# SidBerry_AriettaG25.net
KiCad netlist of a schematic drawn in EAGLE
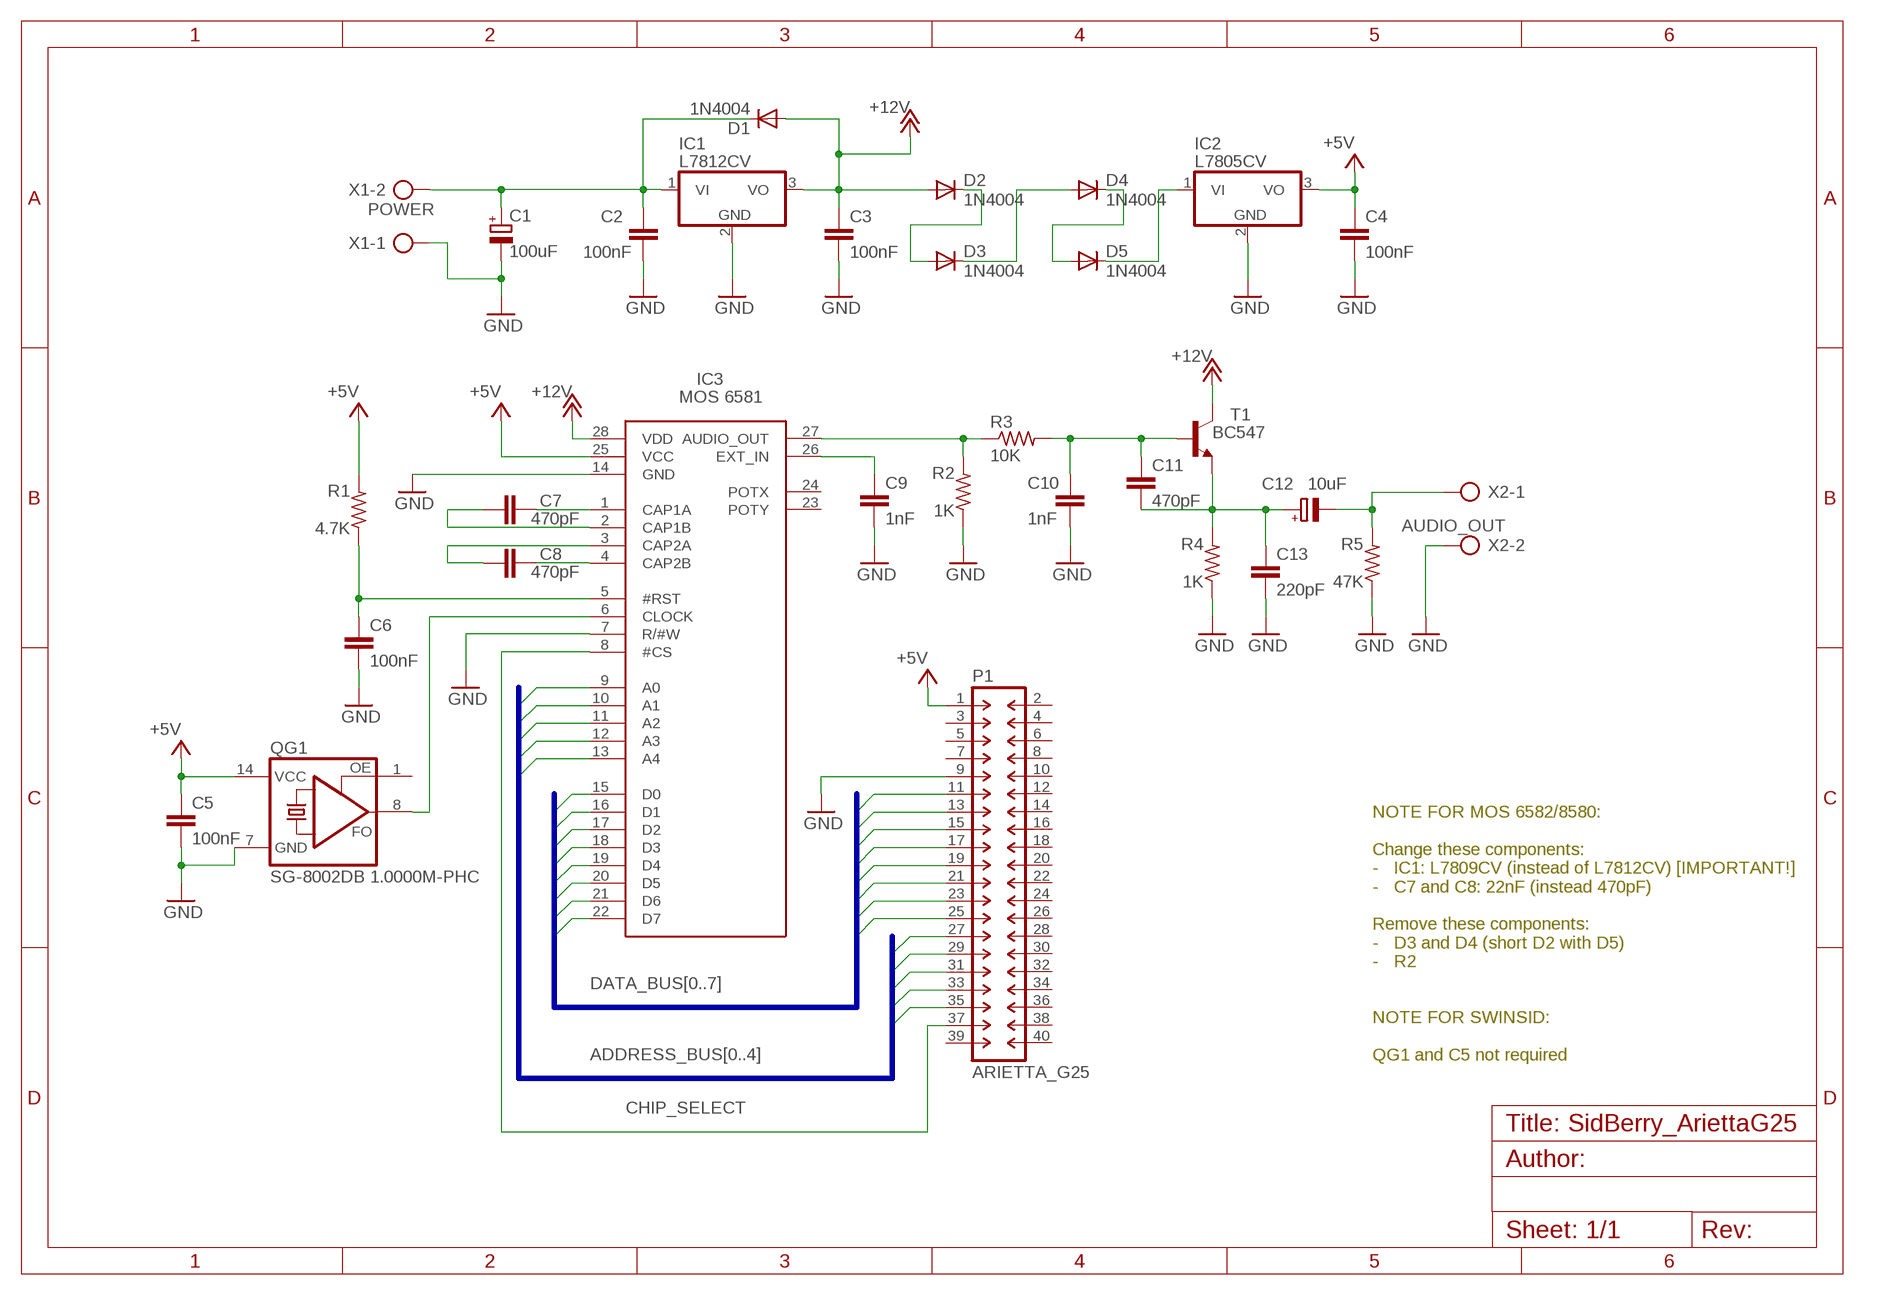
[diagram p0: schematic, sheet 1]

(export (version "E")
  (design (tool "Eeschema 10.0.6"))
  (components
    (comp (ref "C1")
      (value "100uF")
      (footprint "eagle-import:E2,5-6")
      (libsource (lib "eagle-import") (part "CPOL-EUE2.5-6"))
    )
    (comp (ref "C2")
      (value "100nF")
      (footprint "eagle-import:C025-024X044")
      (libsource (lib "eagle-import") (part "C-EU025-024X044"))
    )
    (comp (ref "C3")
      (value "100nF")
      (footprint "eagle-import:C025-024X044")
      (libsource (lib "eagle-import") (part "C-EU025-024X044"))
    )
    (comp (ref "C4")
      (value "100nF")
      (footprint "eagle-import:C025-024X044")
      (libsource (lib "eagle-import") (part "C-EU025-024X044"))
    )
    (comp (ref "C5")
      (value "100nF")
      (footprint "eagle-import:C025-024X044")
      (libsource (lib "eagle-import") (part "C-EU025-024X044"))
    )
    (comp (ref "C6")
      (value "100nF")
      (footprint "eagle-import:C025-024X044")
      (libsource (lib "eagle-import") (part "C-EU025-024X044"))
    )
    (comp (ref "C7")
      (value "470pF")
      (footprint "eagle-import:C025-024X044")
      (libsource (lib "eagle-import") (part "C-EU025-024X044"))
    )
    (comp (ref "C8")
      (value "470pF")
      (footprint "eagle-import:C025-024X044")
      (libsource (lib "eagle-import") (part "C-EU025-024X044"))
    )
    (comp (ref "C9")
      (value "1nF")
      (footprint "eagle-import:C025-024X044")
      (libsource (lib "eagle-import") (part "C-EU025-024X044"))
    )
    (comp (ref "C10")
      (value "1nF")
      (footprint "eagle-import:C025-024X044")
      (libsource (lib "eagle-import") (part "C-EU025-024X044"))
    )
    (comp (ref "C11")
      (value "470pF")
      (footprint "eagle-import:C025-024X044")
      (libsource (lib "eagle-import") (part "C-EU025-024X044"))
    )
    (comp (ref "C12")
      (value "10uF")
      (footprint "eagle-import:E2,5-5")
      (libsource (lib "eagle-import") (part "CPOL-EUE2.5-5"))
    )
    (comp (ref "C13")
      (value "220pF")
      (footprint "eagle-import:C025-024X044")
      (libsource (lib "eagle-import") (part "C-EU025-024X044"))
    )
    (comp (ref "D1")
      (value "1N4004")
      (footprint "eagle-import:DO41-10")
      (libsource (lib "eagle-import") (part "1N4004"))
    )
    (comp (ref "D2")
      (value "1N4004")
      (footprint "eagle-import:DO41-10")
      (libsource (lib "eagle-import") (part "1N4004"))
    )
    (comp (ref "D3")
      (value "1N4004")
      (footprint "eagle-import:DO41-10")
      (libsource (lib "eagle-import") (part "1N4004"))
    )
    (comp (ref "D4")
      (value "1N4004")
      (footprint "eagle-import:DO41-10")
      (libsource (lib "eagle-import") (part "1N4004"))
    )
    (comp (ref "D5")
      (value "1N4004")
      (footprint "eagle-import:DO41-10")
      (libsource (lib "eagle-import") (part "1N4004"))
    )
    (comp (ref "IC1")
      (value "L7812CV")
      (footprint "eagle-import:TO220V")
      (libsource (lib "eagle-import") (part "78TV12"))
    )
    (comp (ref "IC2")
      (value "L7805CV")
      (footprint "eagle-import:TO220V")
      (libsource (lib "eagle-import") (part "78TV05"))
    )
    (comp (ref "IC3")
      (value "MOS 6581")
      (footprint "eagle-import:DIL28-6")
      (fields (field (name "NAME") "IC3"))
      (libsource (lib "eagle-import") (part "SID_6581"))
    )
    (comp (ref "P1")
      (value "ARIETTA_G25")
      (footprint "eagle-import:DIL-100-2X20")
      (libsource (lib "eagle-import") (part "M-2X20-DIL-100"))
    )
    (comp (ref "QG1")
      (value "SG-8002DB 1.0000M-PHC")
      (footprint "eagle-import:SG51")
      (libsource (lib "eagle-import") (part "SG51"))
    )
    (comp (ref "R1")
      (value "4.7K")
      (footprint "eagle-import:0207_10")
      (libsource (lib "eagle-import") (part "R-US_0207/10"))
    )
    (comp (ref "R2")
      (value "1K")
      (footprint "eagle-import:0207_10")
      (libsource (lib "eagle-import") (part "R-US_0207/10"))
    )
    (comp (ref "R3")
      (value "10K")
      (footprint "eagle-import:0207_10")
      (libsource (lib "eagle-import") (part "R-US_0207/10"))
    )
    (comp (ref "R4")
      (value "1K")
      (footprint "eagle-import:0207_10")
      (libsource (lib "eagle-import") (part "R-US_0207/10"))
    )
    (comp (ref "R5")
      (value "47K")
      (footprint "eagle-import:0207_10")
      (libsource (lib "eagle-import") (part "R-US_0207/10"))
    )
    (comp (ref "T1")
      (value "BC547")
      (footprint "eagle-import:TO92-CBE")
      (libsource (lib "eagle-import") (part "-NPN-TO92-CBEBC547"))
    )
    (comp (ref "X1")
      (value "POWER")
      (footprint "eagle-import:AK500_2")
      (libsource (lib "eagle-import") (part "AK500/2"))
    )
    (comp (ref "X2")
      (value "AUDIO_OUT")
      (footprint "eagle-import:AK500_2")
      (libsource (lib "eagle-import") (part "AK500/2"))
    )
  )
  (nets
    (net (code "1") (name "+5V") (class "Default")
      (node (ref "C4") (pin "1") (pinfunction "1_1") (pintype "passive"))
      (node (ref "C5") (pin "1") (pinfunction "1_1") (pintype "passive"))
      (node (ref "IC2") (pin "3") (pinfunction "VO_3") (pintype "passive"))
      (node (ref "IC3") (pin "25") (pinfunction "VCC_25") (pintype "bidirectional"))
      (node (ref "P1") (pin "1") (pinfunction "1_1") (pintype "passive"))
      (node (ref "QG1") (pin "14") (pinfunction "VCC_14") (pintype "power_in"))
      (node (ref "R1") (pin "2") (pinfunction "2_2") (pintype "passive"))
    )
    (net (code "2") (name "+12V") (class "Default")
      (node (ref "C3") (pin "1") (pinfunction "1_1") (pintype "passive"))
      (node (ref "D1") (pin "A") (pinfunction "A_A") (pintype "passive"))
      (node (ref "D2") (pin "A") (pinfunction "A_A") (pintype "passive"))
      (node (ref "IC1") (pin "3") (pinfunction "VO_3") (pintype "passive"))
      (node (ref "IC3") (pin "28") (pinfunction "VDD_28") (pintype "bidirectional"))
      (node (ref "T1") (pin "C") (pinfunction "C_C") (pintype "passive"))
    )
    (net (code "3") (name "/ADDRESS_BUS0") (class "Default")
      (node (ref "IC3") (pin "9") (pinfunction "A0_9") (pintype "bidirectional"))
      (node (ref "P1") (pin "27") (pinfunction "27_27") (pintype "passive"))
    )
    (net (code "4") (name "/ADDRESS_BUS1") (class "Default")
      (node (ref "IC3") (pin "10") (pinfunction "A1_10") (pintype "bidirectional"))
      (node (ref "P1") (pin "29") (pinfunction "29_29") (pintype "passive"))
    )
    (net (code "5") (name "/ADDRESS_BUS2") (class "Default")
      (node (ref "IC3") (pin "11") (pinfunction "A2_11") (pintype "bidirectional"))
      (node (ref "P1") (pin "31") (pinfunction "31_31") (pintype "passive"))
    )
    (net (code "6") (name "/ADDRESS_BUS3") (class "Default")
      (node (ref "IC3") (pin "12") (pinfunction "A3_12") (pintype "bidirectional"))
      (node (ref "P1") (pin "33") (pinfunction "33_33") (pintype "passive"))
    )
    (net (code "7") (name "/ADDRESS_BUS4") (class "Default")
      (node (ref "IC3") (pin "13") (pinfunction "A4_13") (pintype "bidirectional"))
      (node (ref "P1") (pin "35") (pinfunction "35_35") (pintype "passive"))
    )
    (net (code "9") (name "/CHIP_SELECT") (class "Default")
      (node (ref "IC3") (pin "8") (pinfunction "#CS_8") (pintype "bidirectional"))
      (node (ref "P1") (pin "37") (pinfunction "37_37") (pintype "passive"))
    )
    (net (code "10") (name "/DATA_BUS0") (class "Default")
      (node (ref "IC3") (pin "15") (pinfunction "D0_15") (pintype "bidirectional"))
      (node (ref "P1") (pin "25") (pinfunction "25_25") (pintype "passive"))
    )
    (net (code "11") (name "/DATA_BUS1") (class "Default")
      (node (ref "IC3") (pin "16") (pinfunction "D1_16") (pintype "bidirectional"))
      (node (ref "P1") (pin "23") (pinfunction "23_23") (pintype "passive"))
    )
    (net (code "12") (name "/DATA_BUS2") (class "Default")
      (node (ref "IC3") (pin "17") (pinfunction "D2_17") (pintype "bidirectional"))
      (node (ref "P1") (pin "21") (pinfunction "21_21") (pintype "passive"))
    )
    (net (code "13") (name "/DATA_BUS3") (class "Default")
      (node (ref "IC3") (pin "18") (pinfunction "D3_18") (pintype "bidirectional"))
      (node (ref "P1") (pin "19") (pinfunction "19_19") (pintype "passive"))
    )
    (net (code "14") (name "/DATA_BUS4") (class "Default")
      (node (ref "IC3") (pin "19") (pinfunction "D4_19") (pintype "bidirectional"))
      (node (ref "P1") (pin "17") (pinfunction "17_17") (pintype "passive"))
    )
    (net (code "15") (name "/DATA_BUS5") (class "Default")
      (node (ref "IC3") (pin "20") (pinfunction "D5_20") (pintype "bidirectional"))
      (node (ref "P1") (pin "15") (pinfunction "15_15") (pintype "passive"))
    )
    (net (code "16") (name "/DATA_BUS6") (class "Default")
      (node (ref "IC3") (pin "21") (pinfunction "D6_21") (pintype "bidirectional"))
      (node (ref "P1") (pin "13") (pinfunction "13_13") (pintype "passive"))
    )
    (net (code "17") (name "/DATA_BUS7") (class "Default")
      (node (ref "IC3") (pin "22") (pinfunction "D7_22") (pintype "bidirectional"))
      (node (ref "P1") (pin "11") (pinfunction "11_11") (pintype "passive"))
    )
    (net (code "19") (name "GND") (class "Default")
      (node (ref "C1") (pin "-") (pinfunction "-_-") (pintype "passive"))
      (node (ref "C10") (pin "2") (pinfunction "2_2") (pintype "passive"))
      (node (ref "C13") (pin "2") (pinfunction "2_2") (pintype "passive"))
      (node (ref "C2") (pin "2") (pinfunction "2_2") (pintype "passive"))
      (node (ref "C3") (pin "2") (pinfunction "2_2") (pintype "passive"))
      (node (ref "C4") (pin "2") (pinfunction "2_2") (pintype "passive"))
      (node (ref "C5") (pin "2") (pinfunction "2_2") (pintype "passive"))
      (node (ref "C6") (pin "2") (pinfunction "2_2") (pintype "passive"))
      (node (ref "C9") (pin "2") (pinfunction "2_2") (pintype "passive"))
      (node (ref "IC1") (pin "2") (pinfunction "GND_2") (pintype "passive"))
      (node (ref "IC2") (pin "2") (pinfunction "GND_2") (pintype "passive"))
      (node (ref "IC3") (pin "14") (pinfunction "GND_14") (pintype "bidirectional"))
      (node (ref "IC3") (pin "7") (pinfunction "R/#W_7") (pintype "bidirectional"))
      (node (ref "P1") (pin "9") (pinfunction "9_9") (pintype "passive"))
      (node (ref "QG1") (pin "7") (pinfunction "GND_7") (pintype "power_in"))
      (node (ref "R2") (pin "1") (pinfunction "1_1") (pintype "passive"))
      (node (ref "R4") (pin "1") (pinfunction "1_1") (pintype "passive"))
      (node (ref "R5") (pin "1") (pinfunction "1_1") (pintype "passive"))
      (node (ref "X1") (pin "1") (pinfunction "KL_1") (pintype "passive"))
      (node (ref "X2") (pin "2") (pinfunction "KL_2") (pintype "passive"))
    )
    (net (code "20") (name "Net-(C10-Pad1)") (class "Default")
      (node (ref "C10") (pin "1") (pinfunction "1_1") (pintype "passive"))
      (node (ref "C11") (pin "1") (pinfunction "1_1") (pintype "passive"))
      (node (ref "R3") (pin "2") (pinfunction "2_2") (pintype "passive"))
      (node (ref "T1") (pin "B") (pinfunction "B_B") (pintype "passive"))
    )
    (net (code "21") (name "Net-(C11-Pad2)") (class "Default")
      (node (ref "C11") (pin "2") (pinfunction "2_2") (pintype "passive"))
      (node (ref "C12") (pin "+") (pinfunction "+_+") (pintype "passive"))
      (node (ref "C13") (pin "1") (pinfunction "1_1") (pintype "passive"))
      (node (ref "R4") (pin "2") (pinfunction "2_2") (pintype "passive"))
      (node (ref "T1") (pin "E") (pinfunction "E_E") (pintype "passive"))
    )
    (net (code "22") (name "Net-(D2-PadC)") (class "Default")
      (node (ref "D2") (pin "C") (pinfunction "C_C") (pintype "passive"))
      (node (ref "D3") (pin "A") (pinfunction "A_A") (pintype "passive"))
    )
    (net (code "23") (name "Net-(D3-PadC)") (class "Default")
      (node (ref "D3") (pin "C") (pinfunction "C_C") (pintype "passive"))
      (node (ref "D4") (pin "A") (pinfunction "A_A") (pintype "passive"))
    )
    (net (code "24") (name "Net-(D4-PadC)") (class "Default")
      (node (ref "D4") (pin "C") (pinfunction "C_C") (pintype "passive"))
      (node (ref "D5") (pin "A") (pinfunction "A_A") (pintype "passive"))
    )
    (net (code "25") (name "Net-(IC1-VI)") (class "Default")
      (node (ref "C1") (pin "+") (pinfunction "+_+") (pintype "passive"))
      (node (ref "C2") (pin "1") (pinfunction "1_1") (pintype "passive"))
      (node (ref "D1") (pin "C") (pinfunction "C_C") (pintype "passive"))
      (node (ref "IC1") (pin "1") (pinfunction "VI_1") (pintype "input"))
      (node (ref "X1") (pin "2") (pinfunction "KL_2") (pintype "passive"))
    )
    (net (code "26") (name "Net-(IC2-VI)") (class "Default")
      (node (ref "D5") (pin "C") (pinfunction "C_C") (pintype "passive"))
      (node (ref "IC2") (pin "1") (pinfunction "VI_1") (pintype "input"))
    )
    (net (code "27") (name "Net-(IC3-#RST)") (class "Default")
      (node (ref "C6") (pin "1") (pinfunction "1_1") (pintype "passive"))
      (node (ref "IC3") (pin "5") (pinfunction "#RST_5") (pintype "bidirectional"))
      (node (ref "R1") (pin "1") (pinfunction "1_1") (pintype "passive"))
    )
    (net (code "28") (name "Net-(IC3-AUDIO_OUT)") (class "Default")
      (node (ref "IC3") (pin "27") (pinfunction "AUDIO_OUT_27") (pintype "bidirectional"))
      (node (ref "R2") (pin "2") (pinfunction "2_2") (pintype "passive"))
      (node (ref "R3") (pin "1") (pinfunction "1_1") (pintype "passive"))
    )
    (net (code "29") (name "Net-(IC3-CAP1A)") (class "Default")
      (node (ref "C7") (pin "2") (pinfunction "2_2") (pintype "passive"))
      (node (ref "IC3") (pin "1") (pinfunction "CAP1A_1") (pintype "bidirectional"))
    )
    (net (code "30") (name "Net-(IC3-CAP1B)") (class "Default")
      (node (ref "C7") (pin "1") (pinfunction "1_1") (pintype "passive"))
      (node (ref "IC3") (pin "2") (pinfunction "CAP1B_2") (pintype "bidirectional"))
    )
    (net (code "31") (name "Net-(IC3-CAP2A)") (class "Default")
      (node (ref "C8") (pin "1") (pinfunction "1_1") (pintype "passive"))
      (node (ref "IC3") (pin "3") (pinfunction "CAP2A_3") (pintype "bidirectional"))
    )
    (net (code "32") (name "Net-(IC3-CAP2B)") (class "Default")
      (node (ref "C8") (pin "2") (pinfunction "2_2") (pintype "passive"))
      (node (ref "IC3") (pin "4") (pinfunction "CAP2B_4") (pintype "bidirectional"))
    )
    (net (code "33") (name "Net-(IC3-CLOCK)") (class "Default")
      (node (ref "IC3") (pin "6") (pinfunction "CLOCK_6") (pintype "bidirectional"))
      (node (ref "QG1") (pin "8") (pinfunction "FO_8") (pintype "output"))
    )
    (net (code "34") (name "Net-(IC3-EXT_IN)") (class "Default")
      (node (ref "C9") (pin "1") (pinfunction "1_1") (pintype "passive"))
      (node (ref "IC3") (pin "26") (pinfunction "EXT_IN_26") (pintype "bidirectional"))
    )
    (net (code "35") (name "Net-(X2A-KL)") (class "Default")
      (node (ref "C12") (pin "-") (pinfunction "-_-") (pintype "passive"))
      (node (ref "R5") (pin "2") (pinfunction "2_2") (pintype "passive"))
      (node (ref "X2") (pin "1") (pinfunction "KL_1") (pintype "passive"))
    )
    (net (code "36") (name "unconnected-(IC3-POTX-Pad24)") (class "Default")
      (node (ref "IC3") (pin "24") (pinfunction "POTX_24") (pintype "bidirectional"))
    )
    (net (code "37") (name "unconnected-(IC3-POTY-Pad23)") (class "Default")
      (node (ref "IC3") (pin "23") (pinfunction "POTY_23") (pintype "bidirectional"))
    )
    (net (code "38") (name "unconnected-(P1-Pad2)") (class "Default")
      (node (ref "P1") (pin "2") (pinfunction "2_2") (pintype "passive"))
    )
    (net (code "39") (name "unconnected-(P1-Pad3)") (class "Default")
      (node (ref "P1") (pin "3") (pinfunction "3_3") (pintype "passive"))
    )
    (net (code "40") (name "unconnected-(P1-Pad4)") (class "Default")
      (node (ref "P1") (pin "4") (pinfunction "4_4") (pintype "passive"))
    )
    (net (code "41") (name "unconnected-(P1-Pad5)") (class "Default")
      (node (ref "P1") (pin "5") (pinfunction "5_5") (pintype "passive"))
    )
    (net (code "42") (name "unconnected-(P1-Pad6)") (class "Default")
      (node (ref "P1") (pin "6") (pinfunction "6_6") (pintype "passive"))
    )
    (net (code "43") (name "unconnected-(P1-Pad7)") (class "Default")
      (node (ref "P1") (pin "7") (pinfunction "7_7") (pintype "passive"))
    )
    (net (code "44") (name "unconnected-(P1-Pad8)") (class "Default")
      (node (ref "P1") (pin "8") (pinfunction "8_8") (pintype "passive"))
    )
    (net (code "45") (name "unconnected-(P1-Pad10)") (class "Default")
      (node (ref "P1") (pin "10") (pinfunction "10_10") (pintype "passive"))
    )
    (net (code "46") (name "unconnected-(P1-Pad12)") (class "Default")
      (node (ref "P1") (pin "12") (pinfunction "12_12") (pintype "passive"))
    )
    (net (code "47") (name "unconnected-(P1-Pad14)") (class "Default")
      (node (ref "P1") (pin "14") (pinfunction "14_14") (pintype "passive"))
    )
    (net (code "48") (name "unconnected-(P1-Pad16)") (class "Default")
      (node (ref "P1") (pin "16") (pinfunction "16_16") (pintype "passive"))
    )
    (net (code "49") (name "unconnected-(P1-Pad18)") (class "Default")
      (node (ref "P1") (pin "18") (pinfunction "18_18") (pintype "passive"))
    )
    (net (code "50") (name "unconnected-(P1-Pad20)") (class "Default")
      (node (ref "P1") (pin "20") (pinfunction "20_20") (pintype "passive"))
    )
    (net (code "51") (name "unconnected-(P1-Pad22)") (class "Default")
      (node (ref "P1") (pin "22") (pinfunction "22_22") (pintype "passive"))
    )
    (net (code "52") (name "unconnected-(P1-Pad24)") (class "Default")
      (node (ref "P1") (pin "24") (pinfunction "24_24") (pintype "passive"))
    )
    (net (code "53") (name "unconnected-(P1-Pad26)") (class "Default")
      (node (ref "P1") (pin "26") (pinfunction "26_26") (pintype "passive"))
    )
    (net (code "54") (name "unconnected-(P1-Pad28)") (class "Default")
      (node (ref "P1") (pin "28") (pinfunction "28_28") (pintype "passive"))
    )
    (net (code "55") (name "unconnected-(P1-Pad30)") (class "Default")
      (node (ref "P1") (pin "30") (pinfunction "30_30") (pintype "passive"))
    )
    (net (code "56") (name "unconnected-(P1-Pad32)") (class "Default")
      (node (ref "P1") (pin "32") (pinfunction "32_32") (pintype "passive"))
    )
    (net (code "57") (name "unconnected-(P1-Pad34)") (class "Default")
      (node (ref "P1") (pin "34") (pinfunction "34_34") (pintype "passive"))
    )
    (net (code "58") (name "unconnected-(P1-Pad36)") (class "Default")
      (node (ref "P1") (pin "36") (pinfunction "36_36") (pintype "passive"))
    )
    (net (code "59") (name "unconnected-(P1-Pad38)") (class "Default")
      (node (ref "P1") (pin "38") (pinfunction "38_38") (pintype "passive"))
    )
    (net (code "60") (name "unconnected-(P1-Pad39)") (class "Default")
      (node (ref "P1") (pin "39") (pinfunction "39_39") (pintype "passive"))
    )
    (net (code "61") (name "unconnected-(P1-Pad40)") (class "Default")
      (node (ref "P1") (pin "40") (pinfunction "40_40") (pintype "passive"))
    )
    (net (code "62") (name "unconnected-(QG1-OE-Pad1)") (class "Default")
      (node (ref "QG1") (pin "1") (pinfunction "OE_1") (pintype "input"))
    )
  )
)
